# esp8266.net
KiCad netlist of a schematic drawn in EAGLE
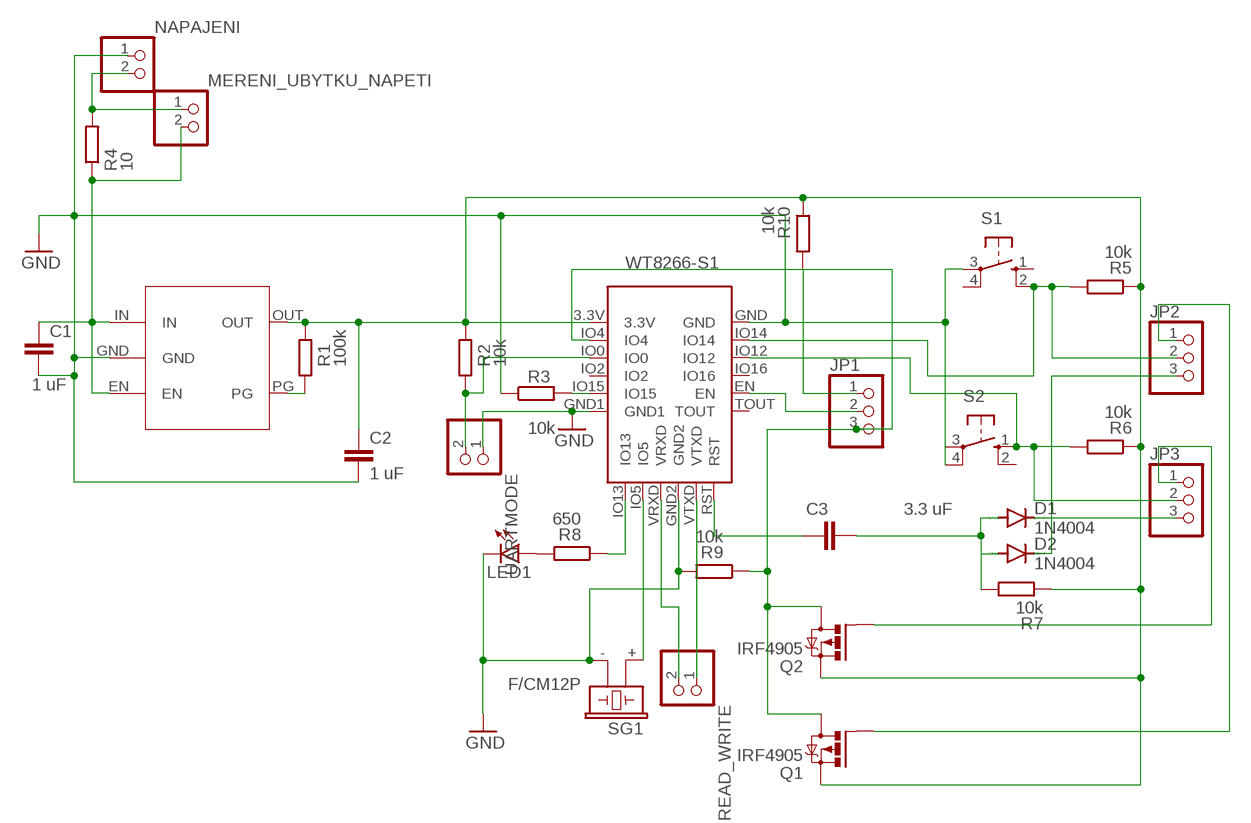
[diagram p0: schematic, sheet 1]

(export (version "E")
  (design (tool "Eeschema 10.0.6"))
  (components
    (comp (ref "C1")
      (value "1 uF")
      (footprint "eagle-import:C2.5-2")
      (libsource (lib "eagle-import") (part "C2.5/2"))
    )
    (comp (ref "C2")
      (value "1 uF")
      (footprint "eagle-import:C2.5-2")
      (libsource (lib "eagle-import") (part "C2.5/2"))
    )
    (comp (ref "C3")
      (value "3.3 uF")
      (footprint "eagle-import:C2.5-2")
      (libsource (lib "eagle-import") (part "C2.5/2"))
    )
    (comp (ref "D1")
      (value "1N4004")
      (footprint "eagle-import:DO41-10")
      (libsource (lib "eagle-import") (part "1N4004"))
    )
    (comp (ref "D2")
      (value "1N4004")
      (footprint "eagle-import:DO41-10")
      (libsource (lib "eagle-import") (part "1N4004"))
    )
    (comp (ref "JP1")
      (value "PINHD-1X3")
      (footprint "eagle-import:1X03")
      (libsource (lib "eagle-import") (part "PINHD-1X3"))
    )
    (comp (ref "JP2")
      (value "PINHD-1X3")
      (footprint "eagle-import:1X03")
      (libsource (lib "eagle-import") (part "PINHD-1X3"))
    )
    (comp (ref "JP3")
      (value "PINHD-1X3")
      (footprint "eagle-import:1X03")
      (libsource (lib "eagle-import") (part "PINHD-1X3"))
    )
    (comp (ref "LED1")
      (value "LED5MM")
      (footprint "eagle-import:LED5MM")
      (libsource (lib "eagle-import") (part "LED5MM"))
    )
    (comp (ref "MERENI_UBYTKU_NAPETI")
      (value "PINHD-1X2")
      (footprint "eagle-import:1X02")
      (libsource (lib "eagle-import") (part "PINHD-1X2"))
    )
    (comp (ref "NAPAJENI")
      (value "PINHD-1X2")
      (footprint "eagle-import:1X02")
      (libsource (lib "eagle-import") (part "PINHD-1X2"))
    )
    (comp (ref "Q1")
      (value "IRF4905")
      (footprint "eagle-import:TO220BH")
      (libsource (lib "eagle-import") (part "IRF4905"))
    )
    (comp (ref "Q2")
      (value "IRF4905")
      (footprint "eagle-import:TO220BH")
      (libsource (lib "eagle-import") (part "IRF4905"))
    )
    (comp (ref "R1")
      (value "100k")
      (footprint "eagle-import:0207_10")
      (libsource (lib "eagle-import") (part "R-EU_0207/10"))
    )
    (comp (ref "R2")
      (value "10k")
      (footprint "eagle-import:0207_10")
      (libsource (lib "eagle-import") (part "R-EU_0207/10"))
    )
    (comp (ref "R3")
      (value "10k")
      (footprint "eagle-import:0207_10")
      (libsource (lib "eagle-import") (part "R-EU_0207/10"))
    )
    (comp (ref "R4")
      (value "10")
      (footprint "eagle-import:0207_10")
      (libsource (lib "eagle-import") (part "R-EU_0207/10"))
    )
    (comp (ref "R5")
      (value "10k")
      (footprint "eagle-import:0207_10")
      (libsource (lib "eagle-import") (part "R-EU_0207/10"))
    )
    (comp (ref "R6")
      (value "10k")
      (footprint "eagle-import:0207_10")
      (libsource (lib "eagle-import") (part "R-EU_0207/10"))
    )
    (comp (ref "R7")
      (value "10k")
      (footprint "eagle-import:0207_10")
      (libsource (lib "eagle-import") (part "R-EU_0207/10"))
    )
    (comp (ref "R8")
      (value "650")
      (footprint "eagle-import:0207_10")
      (libsource (lib "eagle-import") (part "R-EU_0207/10"))
    )
    (comp (ref "R9")
      (value "10k")
      (footprint "eagle-import:0207_10")
      (libsource (lib "eagle-import") (part "R-EU_0207/10"))
    )
    (comp (ref "R10")
      (value "10k")
      (footprint "eagle-import:0207_10")
      (libsource (lib "eagle-import") (part "R-EU_0207/10"))
    )
    (comp (ref "READ_WRITE")
      (value "PINHD-1X2")
      (footprint "eagle-import:1X02")
      (libsource (lib "eagle-import") (part "PINHD-1X2"))
    )
    (comp (ref "S1")
      (value "10-XX")
      (footprint "eagle-import:B3F-10XX")
      (fields (field (name "MPN") "B3F-1000"))
      (libsource (lib "eagle-import") (part "10-XX"))
    )
    (comp (ref "S2")
      (value "10-XX")
      (footprint "eagle-import:B3F-10XX")
      (fields (field (name "MPN") "B3F-1000"))
      (libsource (lib "eagle-import") (part "10-XX"))
    )
    (comp (ref "SG1")
      (value "F/CM12P")
      (footprint "eagle-import:F_CM12P")
      (libsource (lib "eagle-import") (part "F/CM12P"))
    )
    (comp (ref "U$1")
      (value "WT8266-S1")
      (footprint "eagle-import:WT8266-S1")
      (libsource (lib "eagle-import") (part "WT8266-S1"))
    )
    (comp (ref "U$2")
      (value "LDLN030")
      (footprint "eagle-import:LDLN030")
      (libsource (lib "eagle-import") (part "LDLN030"))
    )
    (comp (ref "UARTMODE")
      (value "PINHD-1X2")
      (footprint "eagle-import:1X02")
      (libsource (lib "eagle-import") (part "PINHD-1X2"))
    )
  )
  (nets
    (net (code "1") (name "GND") (class "Default")
      (node (ref "C1") (pin "2") (pinfunction "2_2") (pintype "passive"))
      (node (ref "C2") (pin "2") (pinfunction "2_2") (pintype "passive"))
      (node (ref "LED1") (pin "K") (pinfunction "C_K") (pintype "passive"))
      (node (ref "NAPAJENI") (pin "1") (pinfunction "1_1") (pintype "passive"))
      (node (ref "R3") (pin "1") (pinfunction "1_1") (pintype "passive"))
      (node (ref "R9") (pin "2") (pinfunction "2_2") (pintype "passive"))
      (node (ref "S1") (pin "3") (pinfunction "P_3") (pintype "passive"))
      (node (ref "S2") (pin "4") (pinfunction "P1_4") (pintype "passive"))
      (node (ref "SG1") (pin "-") (pinfunction "2_-") (pintype "passive"))
      (node (ref "U$1") (pin "GND") (pinfunction "GND_GND") (pintype "bidirectional"))
      (node (ref "U$1") (pin "GND1") (pinfunction "GND1_GND1") (pintype "bidirectional"))
      (node (ref "U$1") (pin "GND2") (pinfunction "GND2_GND2") (pintype "bidirectional"))
      (node (ref "U$2") (pin "GND") (pinfunction "GND_GND") (pintype "bidirectional"))
      (node (ref "UARTMODE") (pin "1") (pinfunction "1_1") (pintype "passive"))
    )
    (net (code "2") (name "Net-(C1-Pad1)") (class "Default")
      (node (ref "C1") (pin "1") (pinfunction "1_1") (pintype "passive"))
      (node (ref "MERENI_UBYTKU_NAPETI") (pin "2") (pinfunction "2_2") (pintype "passive"))
      (node (ref "R4") (pin "1") (pinfunction "1_1") (pintype "passive"))
      (node (ref "U$2") (pin "EN") (pinfunction "EN_EN") (pintype "bidirectional"))
      (node (ref "U$2") (pin "IN") (pinfunction "IN_IN") (pintype "bidirectional"))
    )
    (net (code "3") (name "Net-(C2-Pad1)") (class "Default")
      (node (ref "C2") (pin "1") (pinfunction "1_1") (pintype "passive"))
      (node (ref "Q1") (pin "S") (pinfunction "S_S") (pintype "passive"))
      (node (ref "Q2") (pin "S") (pinfunction "S_S") (pintype "passive"))
      (node (ref "R1") (pin "2") (pinfunction "2_2") (pintype "passive"))
      (node (ref "R10") (pin "1") (pinfunction "1_1") (pintype "passive"))
      (node (ref "R2") (pin "2") (pinfunction "2_2") (pintype "passive"))
      (node (ref "R5") (pin "1") (pinfunction "1_1") (pintype "passive"))
      (node (ref "R6") (pin "1") (pinfunction "1_1") (pintype "passive"))
      (node (ref "R7") (pin "1") (pinfunction "1_1") (pintype "passive"))
      (node (ref "U$1") (pin "3.3V") (pinfunction "3.3V_3.3V") (pintype "bidirectional"))
      (node (ref "U$2") (pin "OUT") (pinfunction "OUT_OUT") (pintype "bidirectional"))
    )
    (net (code "4") (name "Net-(C3-Pad1)") (class "Default")
      (node (ref "C3") (pin "1") (pinfunction "1_1") (pintype "passive"))
      (node (ref "U$1") (pin "RST") (pinfunction "RST_RST") (pintype "bidirectional"))
    )
    (net (code "5") (name "Net-(C3-Pad2)") (class "Default")
      (node (ref "C3") (pin "2") (pinfunction "2_2") (pintype "passive"))
      (node (ref "D1") (pin "A") (pinfunction "A_A") (pintype "passive"))
      (node (ref "D2") (pin "A") (pinfunction "A_A") (pintype "passive"))
      (node (ref "R7") (pin "2") (pinfunction "2_2") (pintype "passive"))
    )
    (net (code "6") (name "Net-(D1-PadC)") (class "Default")
      (node (ref "D1") (pin "C") (pinfunction "C_C") (pintype "passive"))
      (node (ref "JP3") (pin "3") (pinfunction "3_3") (pintype "passive"))
    )
    (net (code "7") (name "Net-(D2-PadC)") (class "Default")
      (node (ref "D2") (pin "C") (pinfunction "C_C") (pintype "passive"))
      (node (ref "JP2") (pin "3") (pinfunction "3_3") (pintype "passive"))
    )
    (net (code "8") (name "Net-(JP1-Pad1)") (class "Default")
      (node (ref "JP1") (pin "1") (pinfunction "1_1") (pintype "passive"))
      (node (ref "R10") (pin "2") (pinfunction "2_2") (pintype "passive"))
    )
    (net (code "9") (name "Net-(JP1-Pad2)") (class "Default")
      (node (ref "JP1") (pin "2") (pinfunction "2_2") (pintype "passive"))
      (node (ref "U$1") (pin "EN") (pinfunction "EN_EN") (pintype "bidirectional"))
    )
    (net (code "10") (name "Net-(JP1-Pad3)") (class "Default")
      (node (ref "JP1") (pin "3") (pinfunction "3_3") (pintype "passive"))
      (node (ref "Q1") (pin "D") (pinfunction "D_D") (pintype "passive"))
      (node (ref "Q2") (pin "D") (pinfunction "D_D") (pintype "passive"))
      (node (ref "R9") (pin "1") (pinfunction "1_1") (pintype "passive"))
      (node (ref "U$1") (pin "IO4") (pinfunction "IO4_IO4") (pintype "bidirectional"))
    )
    (net (code "11") (name "Net-(JP2-Pad1)") (class "Default")
      (node (ref "JP2") (pin "1") (pinfunction "1_1") (pintype "passive"))
      (node (ref "Q1") (pin "G") (pinfunction "G_G") (pintype "passive"))
    )
    (net (code "12") (name "Net-(JP3-Pad1)") (class "Default")
      (node (ref "JP3") (pin "1") (pinfunction "1_1") (pintype "passive"))
      (node (ref "Q2") (pin "G") (pinfunction "G_G") (pintype "passive"))
    )
    (net (code "13") (name "Net-(LED1-PadA)") (class "Default")
      (node (ref "LED1") (pin "A") (pinfunction "A_A") (pintype "passive"))
      (node (ref "R8") (pin "2") (pinfunction "2_2") (pintype "passive"))
    )
    (net (code "14") (name "Net-(MERENI_UBYTKU_NAPETI-Pad1)") (class "Default")
      (node (ref "MERENI_UBYTKU_NAPETI") (pin "1") (pinfunction "1_1") (pintype "passive"))
      (node (ref "NAPAJENI") (pin "2") (pinfunction "2_2") (pintype "passive"))
      (node (ref "R4") (pin "2") (pinfunction "2_2") (pintype "passive"))
    )
    (net (code "15") (name "Net-(R1-Pad1)") (class "Default")
      (node (ref "R1") (pin "1") (pinfunction "1_1") (pintype "passive"))
      (node (ref "U$2") (pin "PG") (pinfunction "PG_PG") (pintype "bidirectional"))
    )
    (net (code "16") (name "Net-(R2-Pad1)") (class "Default")
      (node (ref "R2") (pin "1") (pinfunction "1_1") (pintype "passive"))
      (node (ref "U$1") (pin "IO0") (pinfunction "IO0_IO0") (pintype "bidirectional"))
      (node (ref "UARTMODE") (pin "2") (pinfunction "2_2") (pintype "passive"))
    )
    (net (code "17") (name "Net-(R3-Pad2)") (class "Default")
      (node (ref "R3") (pin "2") (pinfunction "2_2") (pintype "passive"))
      (node (ref "U$1") (pin "IO15") (pinfunction "IO15_IO15") (pintype "bidirectional"))
    )
    (net (code "18") (name "Net-(R8-Pad1)") (class "Default")
      (node (ref "R8") (pin "1") (pinfunction "1_1") (pintype "passive"))
      (node (ref "U$1") (pin "IO13") (pinfunction "IO13_IO13") (pintype "bidirectional"))
    )
    (net (code "19") (name "Net-(READ_WRITE-Pad1)") (class "Default")
      (node (ref "READ_WRITE") (pin "1") (pinfunction "1_1") (pintype "passive"))
      (node (ref "U$1") (pin "VTXD") (pinfunction "VTXD_VTXD") (pintype "bidirectional"))
    )
    (net (code "20") (name "Net-(READ_WRITE-Pad2)") (class "Default")
      (node (ref "READ_WRITE") (pin "2") (pinfunction "2_2") (pintype "passive"))
      (node (ref "U$1") (pin "VRXD") (pinfunction "VRXD_VRXD") (pintype "bidirectional"))
    )
    (net (code "21") (name "Net-(S1-S1)") (class "Default")
      (node (ref "JP2") (pin "2") (pinfunction "2_2") (pintype "passive"))
      (node (ref "R5") (pin "2") (pinfunction "2_2") (pintype "passive"))
      (node (ref "S1") (pin "2") (pinfunction "S1_2") (pintype "passive"))
      (node (ref "U$1") (pin "IO14") (pinfunction "IO14_IO14") (pintype "bidirectional"))
    )
    (net (code "22") (name "Net-(S2-S)") (class "Default")
      (node (ref "JP3") (pin "2") (pinfunction "2_2") (pintype "passive"))
      (node (ref "R6") (pin "2") (pinfunction "2_2") (pintype "passive"))
      (node (ref "S2") (pin "1") (pinfunction "S_1") (pintype "passive"))
      (node (ref "U$1") (pin "IO12") (pinfunction "IO12_IO12") (pintype "bidirectional"))
    )
    (net (code "23") (name "Net-(SG1-1)") (class "Default")
      (node (ref "SG1") (pin "+") (pinfunction "1_+") (pintype "passive"))
      (node (ref "U$1") (pin "IO5") (pinfunction "IO5_IO5") (pintype "bidirectional"))
    )
    (net (code "24") (name "unconnected-(S1-P1-Pad4)") (class "Default")
      (node (ref "S1") (pin "4") (pinfunction "P1_4") (pintype "passive"))
    )
    (net (code "25") (name "unconnected-(S1-S-Pad1)") (class "Default")
      (node (ref "S1") (pin "1") (pinfunction "S_1") (pintype "passive"))
    )
    (net (code "26") (name "unconnected-(S2-P-Pad3)") (class "Default")
      (node (ref "S2") (pin "3") (pinfunction "P_3") (pintype "passive"))
    )
    (net (code "27") (name "unconnected-(S2-S1-Pad2)") (class "Default")
      (node (ref "S2") (pin "2") (pinfunction "S1_2") (pintype "passive"))
    )
    (net (code "28") (name "unconnected-(U$1-PadIO2)") (class "Default")
      (node (ref "U$1") (pin "IO2") (pinfunction "IO2_IO2") (pintype "bidirectional"))
    )
    (net (code "29") (name "unconnected-(U$1-PadIO16)") (class "Default")
      (node (ref "U$1") (pin "IO16") (pinfunction "IO16_IO16") (pintype "bidirectional"))
    )
    (net (code "30") (name "unconnected-(U$1-PadTOUT)") (class "Default")
      (node (ref "U$1") (pin "TOUT") (pinfunction "TOUT_TOUT") (pintype "bidirectional"))
    )
  )
)
